# esplash.net
KiCad netlist of a schematic drawn in EAGLE
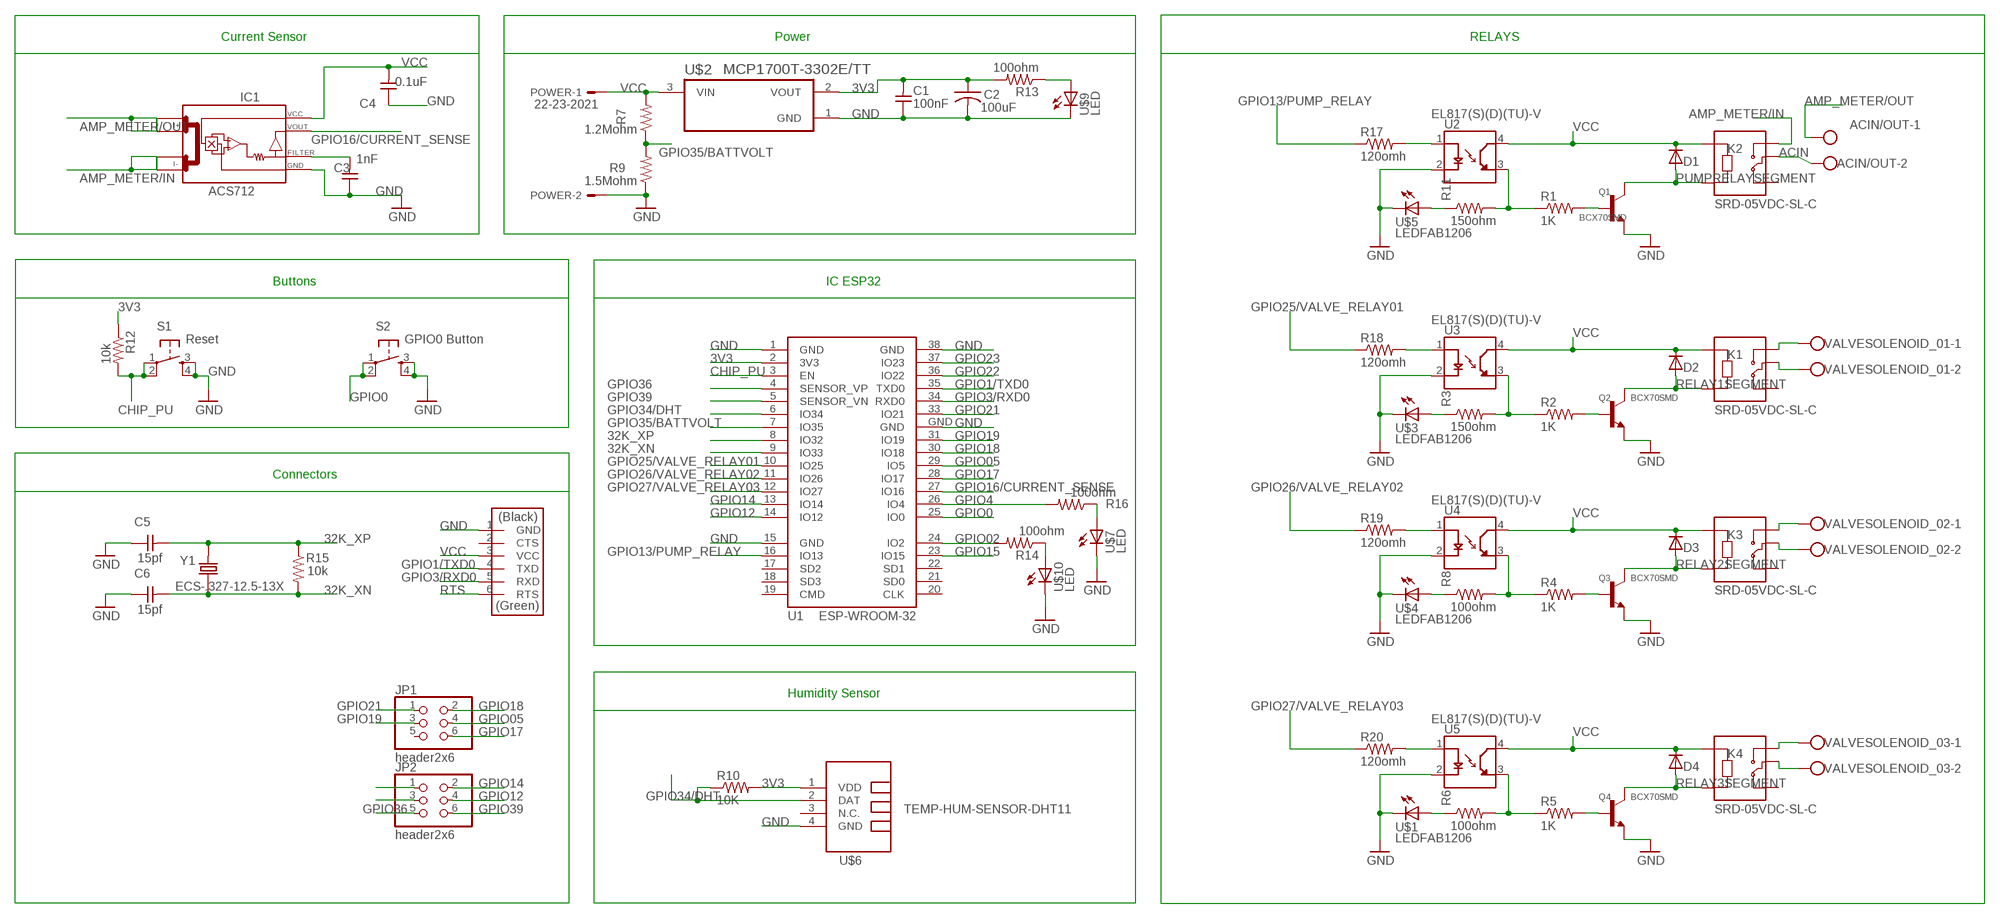
[diagram p0: schematic, sheet 1]

(export (version "E")
  (design (tool "Eeschema 10.0.6"))
  (components
    (comp (ref "ACIN/OUT")
      (value "W237-102")
      (footprint "eagle-import:W237-102")
      (fields (field (name "MPN") "237-102"))
      (libsource (lib "eagle-import") (part "W237-102"))
    )
    (comp (ref "C1")
      (value "100nF")
      (footprint "eagle-import:C1206FAB")
      (libsource (lib "eagle-import") (part "CAP-UNPOLARIZEDFAB"))
    )
    (comp (ref "C2")
      (value "100uF")
      (footprint "eagle-import:C1206FAB")
      (libsource (lib "eagle-import") (part "CAP-US1206FAB"))
    )
    (comp (ref "C3")
      (value "1nF")
      (footprint "eagle-import:C1206FAB")
      (libsource (lib "eagle-import") (part "CAP-UNPOLARIZEDFAB"))
    )
    (comp (ref "C4")
      (value "0.1uF")
      (footprint "eagle-import:C1206FAB")
      (libsource (lib "eagle-import") (part "CAP-UNPOLARIZEDFAB"))
    )
    (comp (ref "C5")
      (value "15pf")
      (footprint "eagle-import:C1206FAB")
      (libsource (lib "eagle-import") (part "CAP-UNPOLARIZEDFAB"))
    )
    (comp (ref "C6")
      (value "15pf")
      (footprint "eagle-import:C1206FAB")
      (libsource (lib "eagle-import") (part "CAP-UNPOLARIZEDFAB"))
    )
    (comp (ref "D1")
      (value "DIODESOD123")
      (footprint "eagle-import:SOD123")
      (libsource (lib "eagle-import") (part "DIODESOD123"))
    )
    (comp (ref "D2")
      (value "DIODESOD123")
      (footprint "eagle-import:SOD123")
      (libsource (lib "eagle-import") (part "DIODESOD123"))
    )
    (comp (ref "D3")
      (value "DIODESOD123")
      (footprint "eagle-import:SOD123")
      (libsource (lib "eagle-import") (part "DIODESOD123"))
    )
    (comp (ref "D4")
      (value "DIODESOD123")
      (footprint "eagle-import:SOD123")
      (libsource (lib "eagle-import") (part "DIODESOD123"))
    )
    (comp (ref "IC1")
      (value "ACS712")
      (footprint "eagle-import:SO08")
      (libsource (lib "eagle-import") (part "ACS712"))
    )
    (comp (ref "JP1")
      (value "header2x6")
      (footprint "eagle-import:2X03")
      (libsource (lib "eagle-import") (part "PINHD-2X3"))
    )
    (comp (ref "JP2")
      (value "header2x6")
      (footprint "eagle-import:2X03")
      (libsource (lib "eagle-import") (part "PINHD-2X3"))
    )
    (comp (ref "K1")
      (value "SRD-05VDC-SL-C")
      (footprint "eagle-import:RELAY_SRD-05VDC-SL-C")
      (fields (field (name "MF") "Songle Relay"))
      (libsource (lib "eagle-import") (part "SRD-05VDC-SL-C"))
    )
    (comp (ref "K2")
      (value "SRD-05VDC-SL-C")
      (footprint "eagle-import:RELAY_SRD-05VDC-SL-C")
      (fields (field (name "MF") "Songle Relay"))
      (libsource (lib "eagle-import") (part "SRD-05VDC-SL-C"))
    )
    (comp (ref "K3")
      (value "SRD-05VDC-SL-C")
      (footprint "eagle-import:RELAY_SRD-05VDC-SL-C")
      (fields (field (name "MF") "Songle Relay"))
      (libsource (lib "eagle-import") (part "SRD-05VDC-SL-C"))
    )
    (comp (ref "K4")
      (value "SRD-05VDC-SL-C")
      (footprint "eagle-import:RELAY_SRD-05VDC-SL-C")
      (fields (field (name "MF") "Songle Relay"))
      (libsource (lib "eagle-import") (part "SRD-05VDC-SL-C"))
    )
    (comp (ref "POWER")
      (value "22-23-2021")
      (footprint "eagle-import:22-23-2021")
      (fields (field (name "MF") "MOLEX"))
      (libsource (lib "eagle-import") (part "22-23-2021"))
    )
    (comp (ref "Q1")
      (value "BCX70SMD")
      (footprint "eagle-import:SOT23")
      (libsource (lib "eagle-import") (part "BCX70SMD"))
    )
    (comp (ref "Q2")
      (value "BCX70SMD")
      (footprint "eagle-import:SOT23")
      (libsource (lib "eagle-import") (part "BCX70SMD"))
    )
    (comp (ref "Q3")
      (value "BCX70SMD")
      (footprint "eagle-import:SOT23")
      (libsource (lib "eagle-import") (part "BCX70SMD"))
    )
    (comp (ref "Q4")
      (value "BCX70SMD")
      (footprint "eagle-import:SOT23")
      (libsource (lib "eagle-import") (part "BCX70SMD"))
    )
    (comp (ref "R1")
      (value "1K")
      (footprint "eagle-import:R1206FAB")
      (libsource (lib "eagle-import") (part "RES-US1206FAB"))
    )
    (comp (ref "R2")
      (value "1K")
      (footprint "eagle-import:R1206FAB")
      (libsource (lib "eagle-import") (part "RES-US1206FAB"))
    )
    (comp (ref "R3")
      (value "150ohm")
      (footprint "eagle-import:R1206FAB")
      (libsource (lib "eagle-import") (part "RES-US1206FAB"))
    )
    (comp (ref "R4")
      (value "1K")
      (footprint "eagle-import:R1206FAB")
      (libsource (lib "eagle-import") (part "RES-US1206FAB"))
    )
    (comp (ref "R5")
      (value "1K")
      (footprint "eagle-import:R1206FAB")
      (libsource (lib "eagle-import") (part "RES-US1206FAB"))
    )
    (comp (ref "R6")
      (value "100ohm")
      (footprint "eagle-import:R1206FAB")
      (libsource (lib "eagle-import") (part "RES-US1206FAB"))
    )
    (comp (ref "R7")
      (value "1.2Mohm")
      (footprint "eagle-import:R1206FAB")
      (libsource (lib "eagle-import") (part "RES-US1206FAB"))
    )
    (comp (ref "R8")
      (value "100ohm")
      (footprint "eagle-import:R1206FAB")
      (libsource (lib "eagle-import") (part "RES-US1206FAB"))
    )
    (comp (ref "R9")
      (value "1.5Mohm")
      (footprint "eagle-import:R1206FAB")
      (libsource (lib "eagle-import") (part "RES-US1206FAB"))
    )
    (comp (ref "R10")
      (value "10K")
      (footprint "eagle-import:R1206FAB")
      (libsource (lib "eagle-import") (part "RES-US1206FAB"))
    )
    (comp (ref "R11")
      (value "150ohm")
      (footprint "eagle-import:R1206FAB")
      (libsource (lib "eagle-import") (part "RES-US1206FAB"))
    )
    (comp (ref "R12")
      (value "10k")
      (footprint "eagle-import:R1206")
      (libsource (lib "eagle-import") (part "RES-US1206"))
    )
    (comp (ref "R13")
      (value "100ohm")
      (footprint "eagle-import:R1206")
      (libsource (lib "eagle-import") (part "RES-US1206"))
    )
    (comp (ref "R14")
      (value "100ohm")
      (footprint "eagle-import:R1206")
      (libsource (lib "eagle-import") (part "RES-US1206"))
    )
    (comp (ref "R15")
      (value "10k")
      (footprint "eagle-import:R1206")
      (libsource (lib "eagle-import") (part "RES-US1206"))
    )
    (comp (ref "R16")
      (value "100ohm")
      (footprint "eagle-import:R1206")
      (libsource (lib "eagle-import") (part "RES-US1206"))
    )
    (comp (ref "R17")
      (value "120omh")
      (footprint "eagle-import:R1206FAB")
      (libsource (lib "eagle-import") (part "RES-US1206FAB"))
    )
    (comp (ref "R18")
      (value "120omh")
      (footprint "eagle-import:R1206FAB")
      (libsource (lib "eagle-import") (part "RES-US1206FAB"))
    )
    (comp (ref "R19")
      (value "120omh")
      (footprint "eagle-import:R1206FAB")
      (libsource (lib "eagle-import") (part "RES-US1206FAB"))
    )
    (comp (ref "R20")
      (value "120omh")
      (footprint "eagle-import:R1206FAB")
      (libsource (lib "eagle-import") (part "RES-US1206FAB"))
    )
    (comp (ref "RTS")
      (value "FTDI-SMD-HEADER")
      (footprint "eagle-import:1X06SMD")
      (libsource (lib "eagle-import") (part "FTDI-SMD-HEADER"))
    )
    (comp (ref "S1")
      (value "Reset")
      (footprint "eagle-import:6MM_SWITCH")
      (libsource (lib "eagle-import") (part "6MM_SWITCH6MM_SWITCH"))
    )
    (comp (ref "S2")
      (value "GPIO0 Button")
      (footprint "eagle-import:6MM_SWITCH")
      (libsource (lib "eagle-import") (part "6MM_SWITCH6MM_SWITCH"))
    )
    (comp (ref "U$1")
      (value "LEDFAB1206")
      (footprint "eagle-import:LED1206FAB")
      (libsource (lib "eagle-import") (part "LEDFAB1206"))
    )
    (comp (ref "U$2")
      (value "MCP1700T-3302E/TT")
      (footprint "eagle-import:SOT95P237X112-3N")
      (fields (field (name "MF") "Microchip Technology"))
      (libsource (lib "eagle-import") (part "MCP1700T-3302E/TT"))
    )
    (comp (ref "U$3")
      (value "LEDFAB1206")
      (footprint "eagle-import:LED1206FAB")
      (libsource (lib "eagle-import") (part "LEDFAB1206"))
    )
    (comp (ref "U$4")
      (value "LEDFAB1206")
      (footprint "eagle-import:LED1206FAB")
      (libsource (lib "eagle-import") (part "LEDFAB1206"))
    )
    (comp (ref "U$5")
      (value "LEDFAB1206")
      (footprint "eagle-import:LED1206FAB")
      (libsource (lib "eagle-import") (part "LEDFAB1206"))
    )
    (comp (ref "U$6")
      (value "TEMP-HUM-SENSOR-DHT11")
      (footprint "eagle-import:TEMP-HUM-SENSOR-DHT11")
      (libsource (lib "eagle-import") (part "TEMP-HUM-SENSOR-DHT11"))
    )
    (comp (ref "U$7")
      (value "LED")
      (footprint "eagle-import:LED1206")
      (libsource (lib "eagle-import") (part "LED"))
    )
    (comp (ref "U$9")
      (value "LED")
      (footprint "eagle-import:LED1206")
      (libsource (lib "eagle-import") (part "LED"))
    )
    (comp (ref "U$10")
      (value "LED")
      (footprint "eagle-import:LED1206")
      (libsource (lib "eagle-import") (part "LED"))
    )
    (comp (ref "U1")
      (value "ESP-WROOM-32")
      (footprint "eagle-import:ESP-WROOM-32")
      (libsource (lib "eagle-import") (part "ESP-WROOM-32"))
    )
    (comp (ref "U2")
      (value "EL817(S)(D)(TU)-V")
      (footprint "eagle-import:SOIC254P1030X460-4N")
      (fields (field (name "MF") "Everlight Electronics"))
      (libsource (lib "eagle-import") (part "EL817(S)(D)(TU)-V"))
    )
    (comp (ref "U3")
      (value "EL817(S)(D)(TU)-V")
      (footprint "eagle-import:SOIC254P1030X460-4N")
      (fields (field (name "MF") "Everlight Electronics"))
      (libsource (lib "eagle-import") (part "EL817(S)(D)(TU)-V"))
    )
    (comp (ref "U4")
      (value "EL817(S)(D)(TU)-V")
      (footprint "eagle-import:SOIC254P1030X460-4N")
      (fields (field (name "MF") "Everlight Electronics"))
      (libsource (lib "eagle-import") (part "EL817(S)(D)(TU)-V"))
    )
    (comp (ref "U5")
      (value "EL817(S)(D)(TU)-V")
      (footprint "eagle-import:SOIC254P1030X460-4N")
      (fields (field (name "MF") "Everlight Electronics"))
      (libsource (lib "eagle-import") (part "EL817(S)(D)(TU)-V"))
    )
    (comp (ref "VALVESOLENOID_01")
      (value "W237-102")
      (footprint "eagle-import:W237-102")
      (fields (field (name "MPN") "237-102"))
      (libsource (lib "eagle-import") (part "W237-102"))
    )
    (comp (ref "VALVESOLENOID_02")
      (value "W237-102")
      (footprint "eagle-import:W237-102")
      (fields (field (name "MPN") "237-102"))
      (libsource (lib "eagle-import") (part "W237-102"))
    )
    (comp (ref "VALVESOLENOID_03")
      (value "W237-102")
      (footprint "eagle-import:W237-102")
      (fields (field (name "MPN") "237-102"))
      (libsource (lib "eagle-import") (part "W237-102"))
    )
    (comp (ref "Y1")
      (value "ECS-.327-12.5-13X")
      (footprint "eagle-import:XTAL_ECS-.327-12.5-13X")
      (fields (field (name "MF") "ECS Inc."))
      (libsource (lib "eagle-import") (part "ECS-.327-12.5-13X"))
    )
  )
  (nets
    (net (code "1") (name "/3V3") (class "Default")
      (node (ref "C1") (pin "2") (pinfunction "2_2") (pintype "passive"))
      (node (ref "C2") (pin "1") (pinfunction "1_1") (pintype "passive"))
      (node (ref "R10") (pin "2") (pinfunction "2_2") (pintype "passive"))
      (node (ref "R12") (pin "1") (pinfunction "1_1") (pintype "passive"))
      (node (ref "R13") (pin "2") (pinfunction "2_2") (pintype "passive"))
      (node (ref "U$2") (pin "2") (pinfunction "VOUT_2") (pintype "output"))
      (node (ref "U$6") (pin "1") (pinfunction "VDD_1") (pintype "power_in"))
      (node (ref "U1") (pin "2") (pinfunction "3V3_2") (pintype "power_in"))
    )
    (net (code "2") (name "/32K_XN") (class "Default")
      (node (ref "C6") (pin "2") (pinfunction "2_2") (pintype "passive"))
      (node (ref "R15") (pin "2") (pinfunction "2_2") (pintype "passive"))
      (node (ref "U1") (pin "9") (pinfunction "IO33_9") (pintype "bidirectional"))
      (node (ref "Y1") (pin "1") (pinfunction "1_1") (pintype "passive"))
    )
    (net (code "3") (name "/32K_XP") (class "Default")
      (node (ref "C5") (pin "2") (pinfunction "2_2") (pintype "passive"))
      (node (ref "R15") (pin "1") (pinfunction "1_1") (pintype "passive"))
      (node (ref "U1") (pin "8") (pinfunction "IO32_8") (pintype "bidirectional"))
      (node (ref "Y1") (pin "2") (pinfunction "2_2") (pintype "passive"))
    )
    (net (code "4") (name "/ACIN") (class "Default")
      (node (ref "ACIN/OUT") (pin "2") (pinfunction "KL_2") (pintype "passive"))
      (node (ref "K2") (pin "COM") (pinfunction "COM_COM") (pintype "passive"))
    )
    (net (code "5") (name "/AMP_METER{slash}IN") (class "Default")
      (node (ref "IC1") (pin "3") (pinfunction "I-_0_3") (pintype "bidirectional"))
      (node (ref "IC1") (pin "4") (pinfunction "I-_1_4") (pintype "bidirectional"))
      (node (ref "K2") (pin "NO") (pinfunction "NO_NO") (pintype "passive"))
    )
    (net (code "6") (name "/AMP_METER{slash}OUT") (class "Default")
      (node (ref "ACIN/OUT") (pin "1") (pinfunction "KL_1") (pintype "passive"))
      (node (ref "IC1") (pin "1") (pinfunction "I+_0_1") (pintype "bidirectional"))
      (node (ref "IC1") (pin "2") (pinfunction "I+_1_2") (pintype "bidirectional"))
    )
    (net (code "7") (name "/CHIP_PU") (class "Default")
      (node (ref "R12") (pin "2") (pinfunction "2_2") (pintype "passive"))
      (node (ref "S1") (pin "1") (pinfunction "P_1") (pintype "passive"))
      (node (ref "S1") (pin "2") (pinfunction "P1_2") (pintype "passive"))
      (node (ref "U1") (pin "3") (pinfunction "EN_3") (pintype "input"))
    )
    (net (code "8") (name "/GPIO0") (class "Default")
      (node (ref "S2") (pin "1") (pinfunction "P_1") (pintype "passive"))
      (node (ref "S2") (pin "2") (pinfunction "P1_2") (pintype "passive"))
      (node (ref "U1") (pin "25") (pinfunction "IO0_25") (pintype "bidirectional"))
    )
    (net (code "9") (name "/GPIO1{slash}TXD0") (class "Default")
      (node (ref "RTS") (pin "4") (pinfunction "TXD_4") (pintype "bidirectional"))
      (node (ref "U1") (pin "35") (pinfunction "TXD0_35") (pintype "bidirectional"))
    )
    (net (code "10") (name "/GPIO02") (class "Default")
      (node (ref "R14") (pin "2") (pinfunction "2_2") (pintype "passive"))
      (node (ref "U1") (pin "24") (pinfunction "IO2_24") (pintype "bidirectional"))
    )
    (net (code "11") (name "/GPIO3{slash}RXD0") (class "Default")
      (node (ref "RTS") (pin "5") (pinfunction "RXD_5") (pintype "bidirectional"))
      (node (ref "U1") (pin "34") (pinfunction "RXD0_34") (pintype "bidirectional"))
    )
    (net (code "12") (name "/GPIO4") (class "Default")
      (node (ref "R16") (pin "2") (pinfunction "2_2") (pintype "passive"))
      (node (ref "U1") (pin "26") (pinfunction "IO4_26") (pintype "bidirectional"))
    )
    (net (code "13") (name "/GPIO05") (class "Default")
      (node (ref "JP1") (pin "4") (pinfunction "4_4") (pintype "passive"))
      (node (ref "U1") (pin "29") (pinfunction "IO5_29") (pintype "bidirectional"))
    )
    (net (code "14") (name "/GPIO12") (class "Default")
      (node (ref "JP2") (pin "4") (pinfunction "4_4") (pintype "passive"))
      (node (ref "U1") (pin "14") (pinfunction "IO12_14") (pintype "bidirectional"))
    )
    (net (code "15") (name "/GPIO13{slash}PUMP_RELAY") (class "Default")
      (node (ref "R17") (pin "1") (pinfunction "1_1") (pintype "passive"))
      (node (ref "U1") (pin "16") (pinfunction "IO13_16") (pintype "bidirectional"))
    )
    (net (code "16") (name "/GPIO14") (class "Default")
      (node (ref "JP2") (pin "2") (pinfunction "2_2") (pintype "passive"))
      (node (ref "U1") (pin "13") (pinfunction "IO14_13") (pintype "bidirectional"))
    )
    (net (code "17") (name "/GPIO15") (class "Default")
      (node (ref "U1") (pin "23") (pinfunction "IO15_23") (pintype "bidirectional"))
    )
    (net (code "18") (name "/GPIO16{slash}CURRENT_SENSE") (class "Default")
      (node (ref "IC1") (pin "7") (pinfunction "VOUT_7") (pintype "output"))
      (node (ref "U1") (pin "27") (pinfunction "IO16_27") (pintype "bidirectional"))
    )
    (net (code "19") (name "/GPIO17") (class "Default")
      (node (ref "JP1") (pin "6") (pinfunction "6_6") (pintype "passive"))
      (node (ref "U1") (pin "28") (pinfunction "IO17_28") (pintype "bidirectional"))
    )
    (net (code "20") (name "/GPIO18") (class "Default")
      (node (ref "JP1") (pin "2") (pinfunction "2_2") (pintype "passive"))
      (node (ref "U1") (pin "30") (pinfunction "IO18_30") (pintype "bidirectional"))
    )
    (net (code "21") (name "/GPIO19") (class "Default")
      (node (ref "JP1") (pin "3") (pinfunction "3_3") (pintype "passive"))
      (node (ref "U1") (pin "31") (pinfunction "IO19_31") (pintype "bidirectional"))
    )
    (net (code "22") (name "/GPIO21") (class "Default")
      (node (ref "JP1") (pin "1") (pinfunction "1_1") (pintype "passive"))
      (node (ref "U1") (pin "33") (pinfunction "IO21_33") (pintype "bidirectional"))
    )
    (net (code "23") (name "/GPIO22") (class "Default")
      (node (ref "U1") (pin "36") (pinfunction "IO22_36") (pintype "bidirectional"))
    )
    (net (code "24") (name "/GPIO23") (class "Default")
      (node (ref "U1") (pin "37") (pinfunction "IO23_37") (pintype "bidirectional"))
    )
    (net (code "25") (name "/GPIO25{slash}VALVE_RELAY01") (class "Default")
      (node (ref "R18") (pin "1") (pinfunction "1_1") (pintype "passive"))
      (node (ref "U1") (pin "10") (pinfunction "IO25_10") (pintype "bidirectional"))
    )
    (net (code "26") (name "/GPIO26{slash}VALVE_RELAY02") (class "Default")
      (node (ref "R19") (pin "1") (pinfunction "1_1") (pintype "passive"))
      (node (ref "U1") (pin "11") (pinfunction "IO26_11") (pintype "bidirectional"))
    )
    (net (code "27") (name "/GPIO27{slash}VALVE_RELAY03") (class "Default")
      (node (ref "R20") (pin "1") (pinfunction "1_1") (pintype "passive"))
      (node (ref "U1") (pin "12") (pinfunction "IO27_12") (pintype "bidirectional"))
    )
    (net (code "28") (name "/GPIO34{slash}DHT") (class "Default")
      (node (ref "R10") (pin "1") (pinfunction "1_1") (pintype "passive"))
      (node (ref "U$6") (pin "2") (pinfunction "DAT_2") (pintype "bidirectional"))
      (node (ref "U1") (pin "6") (pinfunction "IO34_6") (pintype "bidirectional"))
    )
    (net (code "29") (name "/GPIO35{slash}BATTVOLT") (class "Default")
      (node (ref "R7") (pin "1") (pinfunction "1_1") (pintype "passive"))
      (node (ref "R9") (pin "2") (pinfunction "2_2") (pintype "passive"))
      (node (ref "U1") (pin "7") (pinfunction "IO35_7") (pintype "bidirectional"))
    )
    (net (code "30") (name "/GPIO36") (class "Default")
      (node (ref "JP2") (pin "5") (pinfunction "5_5") (pintype "passive"))
      (node (ref "U1") (pin "4") (pinfunction "SENSOR_VP_4") (pintype "bidirectional"))
    )
    (net (code "31") (name "/GPIO39") (class "Default")
      (node (ref "JP2") (pin "6") (pinfunction "6_6") (pintype "passive"))
      (node (ref "U1") (pin "5") (pinfunction "SENSOR_VN_5") (pintype "bidirectional"))
    )
    (net (code "32") (name "/PUMPRELAYSEGMENT") (class "Default")
      (node (ref "D1") (pin "ANODE") (pinfunction "A_ANODE") (pintype "passive"))
      (node (ref "K2") (pin "A2") (pinfunction "A2_A2") (pintype "passive"))
      (node (ref "Q1") (pin "3") (pinfunction "C_3") (pintype "passive"))
    )
    (net (code "33") (name "/RELAY1SEGMENT") (class "Default")
      (node (ref "D2") (pin "ANODE") (pinfunction "A_ANODE") (pintype "passive"))
      (node (ref "K1") (pin "A2") (pinfunction "A2_A2") (pintype "passive"))
      (node (ref "Q2") (pin "3") (pinfunction "C_3") (pintype "passive"))
    )
    (net (code "34") (name "/RELAY2SEGMENT") (class "Default")
      (node (ref "D3") (pin "ANODE") (pinfunction "A_ANODE") (pintype "passive"))
      (node (ref "K3") (pin "A2") (pinfunction "A2_A2") (pintype "passive"))
      (node (ref "Q3") (pin "3") (pinfunction "C_3") (pintype "passive"))
    )
    (net (code "35") (name "/RELAY3SEGMENT") (class "Default")
      (node (ref "D4") (pin "ANODE") (pinfunction "A_ANODE") (pintype "passive"))
      (node (ref "K4") (pin "A2") (pinfunction "A2_A2") (pintype "passive"))
      (node (ref "Q4") (pin "3") (pinfunction "C_3") (pintype "passive"))
    )
    (net (code "36") (name "/RTS") (class "Default")
      (node (ref "RTS") (pin "6") (pinfunction "RTS_6") (pintype "bidirectional"))
    )
    (net (code "37") (name "/VCC") (class "Default")
      (node (ref "C4") (pin "2") (pinfunction "2_2") (pintype "passive"))
      (node (ref "D1") (pin "CATHODE") (pinfunction "C_CATHODE") (pintype "passive"))
      (node (ref "D2") (pin "CATHODE") (pinfunction "C_CATHODE") (pintype "passive"))
      (node (ref "D3") (pin "CATHODE") (pinfunction "C_CATHODE") (pintype "passive"))
      (node (ref "D4") (pin "CATHODE") (pinfunction "C_CATHODE") (pintype "passive"))
      (node (ref "IC1") (pin "8") (pinfunction "VCC_8") (pintype "power_in"))
      (node (ref "K1") (pin "A1") (pinfunction "A1_A1") (pintype "passive"))
      (node (ref "K2") (pin "A1") (pinfunction "A1_A1") (pintype "passive"))
      (node (ref "K3") (pin "A1") (pinfunction "A1_A1") (pintype "passive"))
      (node (ref "K4") (pin "A1") (pinfunction "A1_A1") (pintype "passive"))
      (node (ref "POWER") (pin "1") (pinfunction "S_1") (pintype "passive"))
      (node (ref "R7") (pin "2") (pinfunction "2_2") (pintype "passive"))
      (node (ref "RTS") (pin "3") (pinfunction "VCC_3") (pintype "bidirectional"))
      (node (ref "U$2") (pin "3") (pinfunction "VIN_3") (pintype "input"))
      (node (ref "U2") (pin "4") (pinfunction "CT_4") (pintype "passive"))
      (node (ref "U3") (pin "4") (pinfunction "CT_4") (pintype "passive"))
      (node (ref "U4") (pin "4") (pinfunction "CT_4") (pintype "passive"))
      (node (ref "U5") (pin "4") (pinfunction "CT_4") (pintype "passive"))
    )
    (net (code "38") (name "GND") (class "Default")
      (node (ref "C1") (pin "1") (pinfunction "1_1") (pintype "passive"))
      (node (ref "C2") (pin "2") (pinfunction "2_2") (pintype "passive"))
      (node (ref "C3") (pin "1") (pinfunction "1_1") (pintype "passive"))
      (node (ref "C4") (pin "1") (pinfunction "1_1") (pintype "passive"))
      (node (ref "C5") (pin "1") (pinfunction "1_1") (pintype "passive"))
      (node (ref "C6") (pin "1") (pinfunction "1_1") (pintype "passive"))
      (node (ref "IC1") (pin "5") (pinfunction "GND_5") (pintype "power_in"))
      (node (ref "POWER") (pin "2") (pinfunction "S_2") (pintype "passive"))
      (node (ref "Q1") (pin "2") (pinfunction "E_2") (pintype "passive"))
      (node (ref "Q2") (pin "2") (pinfunction "E_2") (pintype "passive"))
      (node (ref "Q3") (pin "2") (pinfunction "E_2") (pintype "passive"))
      (node (ref "Q4") (pin "2") (pinfunction "E_2") (pintype "passive"))
      (node (ref "R9") (pin "1") (pinfunction "1_1") (pintype "passive"))
      (node (ref "RTS") (pin "1") (pinfunction "GND_1") (pintype "bidirectional"))
      (node (ref "S1") (pin "3") (pinfunction "S_3") (pintype "passive"))
      (node (ref "S1") (pin "4") (pinfunction "S1_4") (pintype "passive"))
      (node (ref "S2") (pin "3") (pinfunction "S_3") (pintype "passive"))
      (node (ref "S2") (pin "4") (pinfunction "S1_4") (pintype "passive"))
      (node (ref "U$1") (pin "2") (pinfunction "C_2") (pintype "passive"))
      (node (ref "U$10") (pin "2") (pinfunction "C_2") (pintype "passive"))
      (node (ref "U$2") (pin "1") (pinfunction "GND_1") (pintype "power_in"))
      (node (ref "U$3") (pin "2") (pinfunction "C_2") (pintype "passive"))
      (node (ref "U$4") (pin "2") (pinfunction "C_2") (pintype "passive"))
      (node (ref "U$5") (pin "2") (pinfunction "C_2") (pintype "passive"))
      (node (ref "U$6") (pin "4") (pinfunction "GND_4") (pintype "power_in"))
      (node (ref "U$7") (pin "2") (pinfunction "C_2") (pintype "passive"))
      (node (ref "U$9") (pin "2") (pinfunction "C_2") (pintype "passive"))
      (node (ref "U1") (pin "1") (pinfunction "GND_1") (pintype "power_in"))
      (node (ref "U1") (pin "15") (pinfunction "GND_15") (pintype "power_in"))
      (node (ref "U1") (pin "38") (pinfunction "GND_38") (pintype "power_in"))
      (node (ref "U1") (pin "GND") (pinfunction "GND_GND") (pintype "power_in"))
      (node (ref "U2") (pin "2") (pinfunction "C_2") (pintype "passive"))
      (node (ref "U3") (pin "2") (pinfunction "C_2") (pintype "passive"))
      (node (ref "U4") (pin "2") (pinfunction "C_2") (pintype "passive"))
      (node (ref "U5") (pin "2") (pinfunction "C_2") (pintype "passive"))
    )
    (net (code "39") (name "Net-(IC1-FILTER)") (class "Default")
      (node (ref "C3") (pin "2") (pinfunction "2_2") (pintype "passive"))
      (node (ref "IC1") (pin "6") (pinfunction "FILTER_6") (pintype "bidirectional"))
    )
    (net (code "40") (name "Net-(Q1-B)") (class "Default")
      (node (ref "Q1") (pin "1") (pinfunction "B_1") (pintype "passive"))
      (node (ref "R1") (pin "2") (pinfunction "2_2") (pintype "passive"))
    )
    (net (code "41") (name "Net-(Q2-B)") (class "Default")
      (node (ref "Q2") (pin "1") (pinfunction "B_1") (pintype "passive"))
      (node (ref "R2") (pin "2") (pinfunction "2_2") (pintype "passive"))
    )
    (net (code "42") (name "Net-(Q3-B)") (class "Default")
      (node (ref "Q3") (pin "1") (pinfunction "B_1") (pintype "passive"))
      (node (ref "R4") (pin "2") (pinfunction "2_2") (pintype "passive"))
    )
    (net (code "43") (name "Net-(Q4-B)") (class "Default")
      (node (ref "Q4") (pin "1") (pinfunction "B_1") (pintype "passive"))
      (node (ref "R5") (pin "2") (pinfunction "2_2") (pintype "passive"))
    )
    (net (code "44") (name "Net-(U$1-A)") (class "Default")
      (node (ref "R6") (pin "1") (pinfunction "1_1") (pintype "passive"))
      (node (ref "U$1") (pin "1") (pinfunction "A_1") (pintype "passive"))
    )
    (net (code "45") (name "Net-(U$3-A)") (class "Default")
      (node (ref "R3") (pin "1") (pinfunction "1_1") (pintype "passive"))
      (node (ref "U$3") (pin "1") (pinfunction "A_1") (pintype "passive"))
    )
    (net (code "46") (name "Net-(U$4-A)") (class "Default")
      (node (ref "R8") (pin "1") (pinfunction "1_1") (pintype "passive"))
      (node (ref "U$4") (pin "1") (pinfunction "A_1") (pintype "passive"))
    )
    (net (code "47") (name "Net-(U$5-A)") (class "Default")
      (node (ref "R11") (pin "1") (pinfunction "1_1") (pintype "passive"))
      (node (ref "U$5") (pin "1") (pinfunction "A_1") (pintype "passive"))
    )
    (net (code "48") (name "Net-(U$7-A)") (class "Default")
      (node (ref "R16") (pin "1") (pinfunction "1_1") (pintype "passive"))
      (node (ref "U$7") (pin "1") (pinfunction "A_1") (pintype "passive"))
    )
    (net (code "49") (name "Net-(U$9-A)") (class "Default")
      (node (ref "R13") (pin "1") (pinfunction "1_1") (pintype "passive"))
      (node (ref "U$9") (pin "1") (pinfunction "A_1") (pintype "passive"))
    )
    (net (code "50") (name "Net-(U$10-A)") (class "Default")
      (node (ref "R14") (pin "1") (pinfunction "1_1") (pintype "passive"))
      (node (ref "U$10") (pin "1") (pinfunction "A_1") (pintype "passive"))
    )
    (net (code "51") (name "Net-(U2-A)") (class "Default")
      (node (ref "R17") (pin "2") (pinfunction "2_2") (pintype "passive"))
      (node (ref "U2") (pin "1") (pinfunction "A_1") (pintype "passive"))
    )
    (net (code "52") (name "Net-(U2-ET)") (class "Default")
      (node (ref "R1") (pin "1") (pinfunction "1_1") (pintype "passive"))
      (node (ref "R11") (pin "2") (pinfunction "2_2") (pintype "passive"))
      (node (ref "U2") (pin "3") (pinfunction "ET_3") (pintype "passive"))
    )
    (net (code "53") (name "Net-(U3-A)") (class "Default")
      (node (ref "R18") (pin "2") (pinfunction "2_2") (pintype "passive"))
      (node (ref "U3") (pin "1") (pinfunction "A_1") (pintype "passive"))
    )
    (net (code "54") (name "Net-(U3-ET)") (class "Default")
      (node (ref "R2") (pin "1") (pinfunction "1_1") (pintype "passive"))
      (node (ref "R3") (pin "2") (pinfunction "2_2") (pintype "passive"))
      (node (ref "U3") (pin "3") (pinfunction "ET_3") (pintype "passive"))
    )
    (net (code "55") (name "Net-(U4-A)") (class "Default")
      (node (ref "R19") (pin "2") (pinfunction "2_2") (pintype "passive"))
      (node (ref "U4") (pin "1") (pinfunction "A_1") (pintype "passive"))
    )
    (net (code "56") (name "Net-(U4-ET)") (class "Default")
      (node (ref "R4") (pin "1") (pinfunction "1_1") (pintype "passive"))
      (node (ref "R8") (pin "2") (pinfunction "2_2") (pintype "passive"))
      (node (ref "U4") (pin "3") (pinfunction "ET_3") (pintype "passive"))
    )
    (net (code "57") (name "Net-(U5-A)") (class "Default")
      (node (ref "R20") (pin "2") (pinfunction "2_2") (pintype "passive"))
      (node (ref "U5") (pin "1") (pinfunction "A_1") (pintype "passive"))
    )
    (net (code "58") (name "Net-(U5-ET)") (class "Default")
      (node (ref "R5") (pin "1") (pinfunction "1_1") (pintype "passive"))
      (node (ref "R6") (pin "2") (pinfunction "2_2") (pintype "passive"))
      (node (ref "U5") (pin "3") (pinfunction "ET_3") (pintype "passive"))
    )
    (net (code "59") (name "Net-(VALVESOLENOID_01A-KL)") (class "Default")
      (node (ref "K1") (pin "NO") (pinfunction "NO_NO") (pintype "passive"))
      (node (ref "VALVESOLENOID_01") (pin "1") (pinfunction "KL_1") (pintype "passive"))
    )
    (net (code "60") (name "Net-(VALVESOLENOID_01B-KL)") (class "Default")
      (node (ref "K1") (pin "COM") (pinfunction "COM_COM") (pintype "passive"))
      (node (ref "VALVESOLENOID_01") (pin "2") (pinfunction "KL_2") (pintype "passive"))
    )
    (net (code "61") (name "Net-(VALVESOLENOID_02A-KL)") (class "Default")
      (node (ref "K3") (pin "NO") (pinfunction "NO_NO") (pintype "passive"))
      (node (ref "VALVESOLENOID_02") (pin "1") (pinfunction "KL_1") (pintype "passive"))
    )
    (net (code "62") (name "Net-(VALVESOLENOID_02B-KL)") (class "Default")
      (node (ref "K3") (pin "COM") (pinfunction "COM_COM") (pintype "passive"))
      (node (ref "VALVESOLENOID_02") (pin "2") (pinfunction "KL_2") (pintype "passive"))
    )
    (net (code "63") (name "Net-(VALVESOLENOID_03A-KL)") (class "Default")
      (node (ref "K4") (pin "NO") (pinfunction "NO_NO") (pintype "passive"))
      (node (ref "VALVESOLENOID_03") (pin "1") (pinfunction "KL_1") (pintype "passive"))
    )
    (net (code "64") (name "Net-(VALVESOLENOID_03B-KL)") (class "Default")
      (node (ref "K4") (pin "COM") (pinfunction "COM_COM") (pintype "passive"))
      (node (ref "VALVESOLENOID_03") (pin "2") (pinfunction "KL_2") (pintype "passive"))
    )
    (net (code "65") (name "unconnected-(JP1-Pad5)") (class "Default")
      (node (ref "JP1") (pin "5") (pinfunction "5_5") (pintype "passive"))
    )
    (net (code "66") (name "unconnected-(JP2-Pad1)") (class "Default")
      (node (ref "JP2") (pin "1") (pinfunction "1_1") (pintype "passive"))
    )
    (net (code "67") (name "unconnected-(JP2-Pad3)") (class "Default")
      (node (ref "JP2") (pin "3") (pinfunction "3_3") (pintype "passive"))
    )
    (net (code "68") (name "unconnected-(K1-PadNC)") (class "Default")
      (node (ref "K1") (pin "NC") (pinfunction "NC_NC") (pintype "passive"))
    )
    (net (code "69") (name "unconnected-(K2-PadNC)") (class "Default")
      (node (ref "K2") (pin "NC") (pinfunction "NC_NC") (pintype "passive"))
    )
    (net (code "70") (name "unconnected-(K3-PadNC)") (class "Default")
      (node (ref "K3") (pin "NC") (pinfunction "NC_NC") (pintype "passive"))
    )
    (net (code "71") (name "unconnected-(K4-PadNC)") (class "Default")
      (node (ref "K4") (pin "NC") (pinfunction "NC_NC") (pintype "passive"))
    )
    (net (code "72") (name "unconnected-(RTS-CTS-Pad2)") (class "Default")
      (node (ref "RTS") (pin "2") (pinfunction "CTS_2") (pintype "bidirectional"))
    )
    (net (code "73") (name "unconnected-(U$6-N.C.-Pad3)") (class "Default")
      (node (ref "U$6") (pin "3") (pinfunction "N.C._3") (pintype "passive"))
    )
    (net (code "74") (name "unconnected-(U1-CLK-Pad20)") (class "Default")
      (node (ref "U1") (pin "20") (pinfunction "CLK_20") (pintype "bidirectional"))
    )
    (net (code "75") (name "unconnected-(U1-CMD-Pad19)") (class "Default")
      (node (ref "U1") (pin "19") (pinfunction "CMD_19") (pintype "bidirectional"))
    )
    (net (code "76") (name "unconnected-(U1-SD0-Pad21)") (class "Default")
      (node (ref "U1") (pin "21") (pinfunction "SD0_21") (pintype "bidirectional"))
    )
    (net (code "77") (name "unconnected-(U1-SD1-Pad22)") (class "Default")
      (node (ref "U1") (pin "22") (pinfunction "SD1_22") (pintype "bidirectional"))
    )
    (net (code "78") (name "unconnected-(U1-SD2-Pad17)") (class "Default")
      (node (ref "U1") (pin "17") (pinfunction "SD2_17") (pintype "bidirectional"))
    )
    (net (code "79") (name "unconnected-(U1-SD3-Pad18)") (class "Default")
      (node (ref "U1") (pin "18") (pinfunction "SD3_18") (pintype "bidirectional"))
    )
  )
)
